# ChristmasTree.net
KiCad netlist of a schematic drawn in Altium Designer
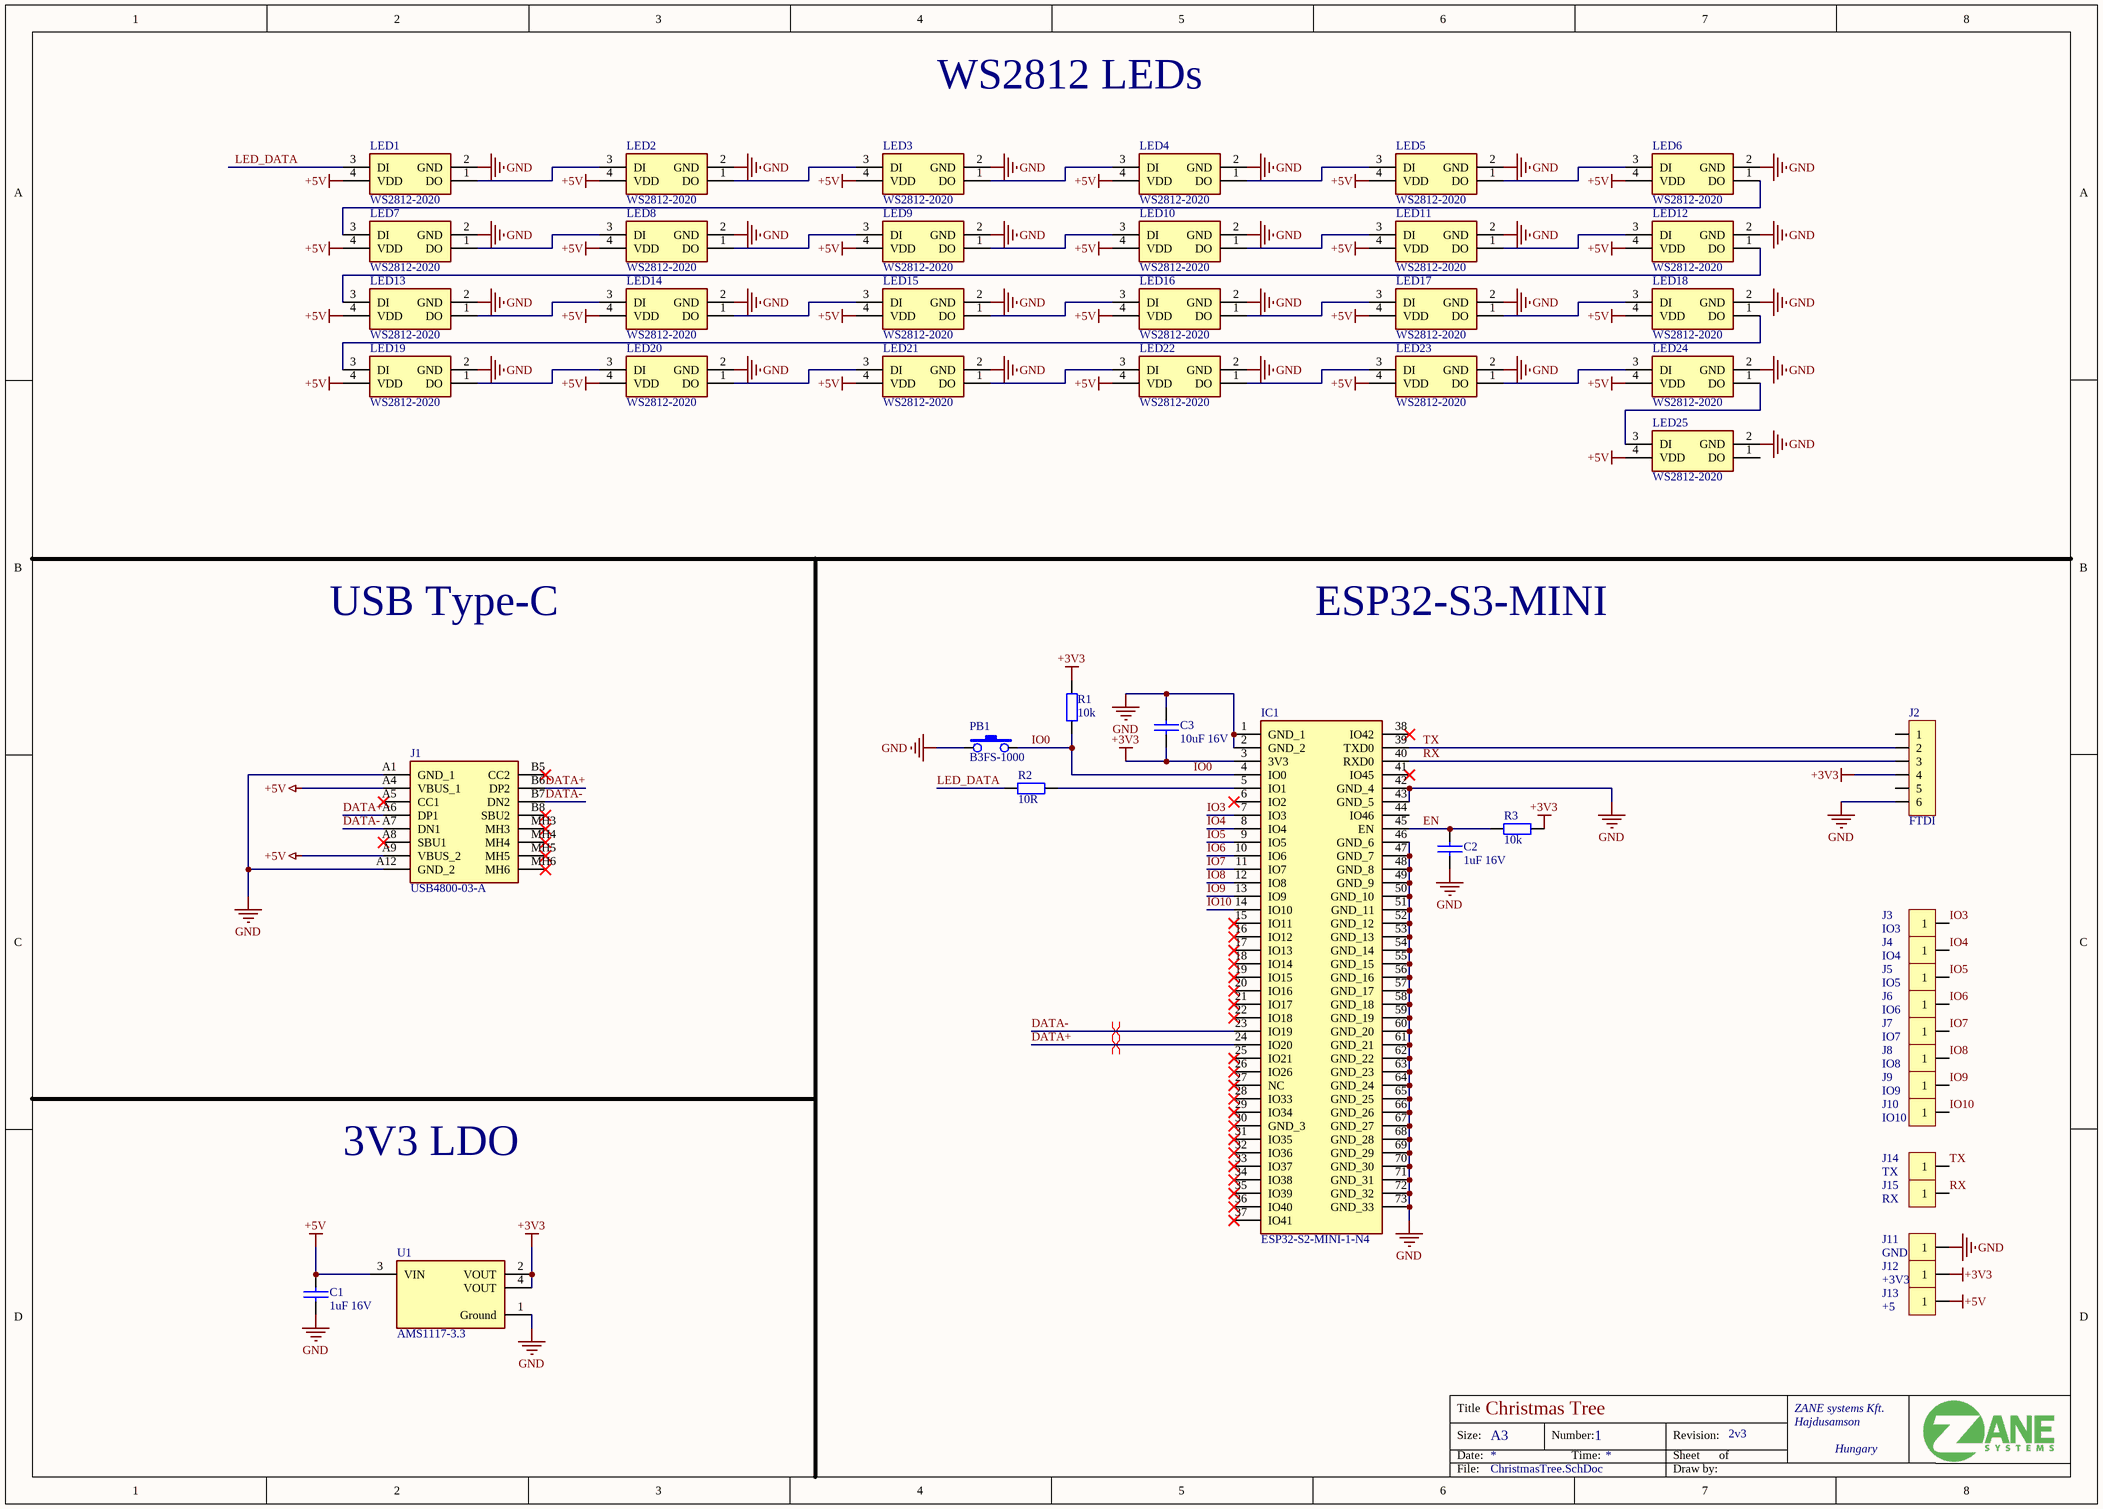
[diagram p0: ChristmasTree.SchDoc]

(export (version "E")
  (design (tool "Eeschema 10.0.6"))
  (components
    (comp (ref "C1")
      (value "1uF 16V")
      (footprint "Z_0603_C")
      (description "=Value")
      (fields (field (name "MF") "SAMSUNG"))
      (libsource (lib "miniscanner_schlib") (part "CAP_0805"))
    )
    (comp (ref "C2")
      (value "1uF 16V")
      (footprint "Z_0603_C")
      (description "=Value")
      (fields (field (name "MF") "SAMSUNG"))
      (libsource (lib "miniscanner_schlib") (part "CAP_0805"))
    )
    (comp (ref "C3")
      (value "10uF 16V")
      (footprint "Z_0603_C")
      (description "=Value")
      (fields (field (name "MF") "SAMSUNG"))
      (libsource (lib "miniscanner_schlib") (part "CAP_0805"))
    )
    (comp (ref "IC1")
      (value "ESP32-S2-MINI-1-N4")
      (footprint "SamacSys:ESP32S2MINI1N4")
      (description "Integrated Circuit")
      (fields (field (name "MOUSER PART NUMBER") "356-ESP32-S2-MINI-1"))
      (libsource (lib "SamacSys") (part "ESP32-S2-MINI-1-N4"))
    )
    (comp (ref "J1")
      (value "USB4800-03-A")
      (footprint "USB480003A")
      (description "Connector")
      (libsource (lib "*") (part "USB4800-03-A"))
    )
    (comp (ref "J2")
      (value "FTDI")
      (footprint "TUSKE1X6_2.54MM")
      (libsource (lib "zane_sch_lib") (part "CON6"))
    )
    (comp (ref "J3") (value "IO3") (footprint "SMD_PAD") (libsource (lib "zane_sch_lib") (part "CON1")))
    (comp (ref "J4") (value "IO4") (footprint "SMD_PAD") (libsource (lib "zane_sch_lib") (part "CON1")))
    (comp (ref "J5") (value "IO5") (footprint "SMD_PAD") (libsource (lib "zane_sch_lib") (part "CON1")))
    (comp (ref "J6") (value "IO6") (footprint "SMD_PAD") (libsource (lib "zane_sch_lib") (part "CON1")))
    (comp (ref "J7") (value "IO7") (footprint "SMD_PAD") (libsource (lib "zane_sch_lib") (part "CON1")))
    (comp (ref "J8") (value "IO8") (footprint "SMD_PAD") (libsource (lib "zane_sch_lib") (part "CON1")))
    (comp (ref "J9") (value "IO9") (footprint "SMD_PAD") (libsource (lib "zane_sch_lib") (part "CON1")))
    (comp (ref "J10") (value "IO10") (footprint "SMD_PAD") (libsource (lib "zane_sch_lib") (part "CON1")))
    (comp (ref "J11") (value "GND") (footprint "SMD_PAD") (libsource (lib "zane_sch_lib") (part "CON1")))
    (comp (ref "J12") (value "+3V3") (footprint "SMD_PAD") (libsource (lib "zane_sch_lib") (part "CON1")))
    (comp (ref "J13") (value "+5") (footprint "SMD_PAD") (libsource (lib "zane_sch_lib") (part "CON1")))
    (comp (ref "J14") (value "TX") (footprint "SMD_PAD") (libsource (lib "zane_sch_lib") (part "CON1")))
    (comp (ref "J15") (value "RX") (footprint "SMD_PAD") (libsource (lib "zane_sch_lib") (part "CON1")))
    (comp (ref "LED1")
      (value "WS2812-2020")
      (footprint "WS28122020")
      (description "LED")
      (libsource (lib "*") (part "WS2812-2020"))
    )
    (comp (ref "LED2")
      (value "WS2812-2020")
      (footprint "WS28122020")
      (description "LED")
      (libsource (lib "*") (part "WS2812-2020"))
    )
    (comp (ref "LED3")
      (value "WS2812-2020")
      (footprint "WS28122020")
      (description "LED")
      (libsource (lib "*") (part "WS2812-2020"))
    )
    (comp (ref "LED4")
      (value "WS2812-2020")
      (footprint "WS28122020")
      (description "LED")
      (libsource (lib "*") (part "WS2812-2020"))
    )
    (comp (ref "LED5")
      (value "WS2812-2020")
      (footprint "WS28122020")
      (description "LED")
      (libsource (lib "*") (part "WS2812-2020"))
    )
    (comp (ref "LED6")
      (value "WS2812-2020")
      (footprint "WS28122020")
      (description "LED")
      (libsource (lib "*") (part "WS2812-2020"))
    )
    (comp (ref "LED7")
      (value "WS2812-2020")
      (footprint "WS28122020")
      (description "LED")
      (libsource (lib "*") (part "WS2812-2020"))
    )
    (comp (ref "LED8")
      (value "WS2812-2020")
      (footprint "WS28122020")
      (description "LED")
      (libsource (lib "*") (part "WS2812-2020"))
    )
    (comp (ref "LED9")
      (value "WS2812-2020")
      (footprint "WS28122020")
      (description "LED")
      (libsource (lib "*") (part "WS2812-2020"))
    )
    (comp (ref "LED10")
      (value "WS2812-2020")
      (footprint "WS28122020")
      (description "LED")
      (libsource (lib "*") (part "WS2812-2020"))
    )
    (comp (ref "LED11")
      (value "WS2812-2020")
      (footprint "WS28122020")
      (description "LED")
      (libsource (lib "*") (part "WS2812-2020"))
    )
    (comp (ref "LED12")
      (value "WS2812-2020")
      (footprint "WS28122020")
      (description "LED")
      (libsource (lib "*") (part "WS2812-2020"))
    )
    (comp (ref "LED13")
      (value "WS2812-2020")
      (footprint "WS28122020")
      (description "LED")
      (libsource (lib "*") (part "WS2812-2020"))
    )
    (comp (ref "LED14")
      (value "WS2812-2020")
      (footprint "WS28122020")
      (description "LED")
      (libsource (lib "*") (part "WS2812-2020"))
    )
    (comp (ref "LED15")
      (value "WS2812-2020")
      (footprint "WS28122020")
      (description "LED")
      (libsource (lib "*") (part "WS2812-2020"))
    )
    (comp (ref "LED16")
      (value "WS2812-2020")
      (footprint "WS28122020")
      (description "LED")
      (libsource (lib "*") (part "WS2812-2020"))
    )
    (comp (ref "LED17")
      (value "WS2812-2020")
      (footprint "WS28122020")
      (description "LED")
      (libsource (lib "*") (part "WS2812-2020"))
    )
    (comp (ref "LED18")
      (value "WS2812-2020")
      (footprint "WS28122020")
      (description "LED")
      (libsource (lib "*") (part "WS2812-2020"))
    )
    (comp (ref "LED19")
      (value "WS2812-2020")
      (footprint "WS28122020")
      (description "LED")
      (libsource (lib "*") (part "WS2812-2020"))
    )
    (comp (ref "LED20")
      (value "WS2812-2020")
      (footprint "WS28122020")
      (description "LED")
      (libsource (lib "*") (part "WS2812-2020"))
    )
    (comp (ref "LED21")
      (value "WS2812-2020")
      (footprint "WS28122020")
      (description "LED")
      (libsource (lib "*") (part "WS2812-2020"))
    )
    (comp (ref "LED22")
      (value "WS2812-2020")
      (footprint "WS28122020")
      (description "LED")
      (libsource (lib "*") (part "WS2812-2020"))
    )
    (comp (ref "LED23")
      (value "WS2812-2020")
      (footprint "WS28122020")
      (description "LED")
      (libsource (lib "*") (part "WS2812-2020"))
    )
    (comp (ref "LED24")
      (value "WS2812-2020")
      (footprint "WS28122020")
      (description "LED")
      (libsource (lib "*") (part "WS2812-2020"))
    )
    (comp (ref "LED25")
      (value "WS2812-2020")
      (footprint "WS28122020")
      (description "LED")
      (libsource (lib "*") (part "WS2812-2020"))
    )
    (comp (ref "PB1")
      (value "B3FS-1000")
      (footprint "dtsm3")
      (description "Push Button")
      (libsource (lib "zane_sch_lib") (part "Push Button 2pin"))
    )
    (comp (ref "R1")
      (value "10k")
      (footprint "z_0603_r")
      (fields (field (name "MF") "ROYAL OHM"))
      (libsource (lib "") (part "Resistor_1"))
    )
    (comp (ref "R2")
      (value "10R")
      (footprint "z_0603_r")
      (fields (field (name "MF") "ROYAL OHM"))
      (libsource (lib "fit5mini_01") (part "Resistor"))
    )
    (comp (ref "R3")
      (value "10k")
      (footprint "z_0603_r")
      (fields (field (name "MF") "ROYAL OHM"))
      (libsource (lib "fit5mini_01") (part "Resistor"))
    )
    (comp (ref "U1")
      (value "AMS1117-3.3")
      (footprint "FP-AMS1117-IPC_C")
      (description "LDO Voltage Regulators 1A, 3.3V")
      (fields
        (field (name "OCTOPART") "https://octopart.com/ams1117-3.3-advanced+monolithic+systems-25899300")
        (field (name "MANUFACTURER") "Advanced Monolithic Systems")
      )
      (libsource (lib "Altium Content Vault") (part "8bdbb5f8e77002000e30dd2845d0354"))
    )
  )
  (nets
    (net (code "1") (name "+3V3") (class "Default")
      (node (ref "C3") (pin "1") (pinfunction "1_1") (pintype "passive"))
      (node (ref "IC1") (pin "3") (pinfunction "3V3_3") (pintype "passive"))
      (node (ref "J12") (pin "1") (pinfunction "1_1") (pintype "passive"))
      (node (ref "J2") (pin "4") (pinfunction "4_4") (pintype "passive"))
      (node (ref "R1") (pin "2") (pinfunction "2_2") (pintype "passive"))
      (node (ref "R3") (pin "1") (pinfunction "1_1") (pintype "passive"))
      (node (ref "U1") (pin "2") (pinfunction "VOUT_2") (pintype "passive"))
      (node (ref "U1") (pin "4") (pinfunction "VOUT_4") (pintype "passive"))
    )
    (net (code "2") (name "+5V") (class "Default")
      (node (ref "C1") (pin "1") (pinfunction "1_1") (pintype "passive"))
      (node (ref "J1") (pin "A4") (pinfunction "VBUS_1_A4") (pintype "passive"))
      (node (ref "J1") (pin "A9") (pinfunction "VBUS_2_A9") (pintype "passive"))
      (node (ref "J13") (pin "1") (pinfunction "1_1") (pintype "passive"))
      (node (ref "LED1") (pin "4") (pinfunction "VDD_4") (pintype "passive"))
      (node (ref "LED10") (pin "4") (pinfunction "VDD_4") (pintype "passive"))
      (node (ref "LED11") (pin "4") (pinfunction "VDD_4") (pintype "passive"))
      (node (ref "LED12") (pin "4") (pinfunction "VDD_4") (pintype "passive"))
      (node (ref "LED13") (pin "4") (pinfunction "VDD_4") (pintype "passive"))
      (node (ref "LED14") (pin "4") (pinfunction "VDD_4") (pintype "passive"))
      (node (ref "LED15") (pin "4") (pinfunction "VDD_4") (pintype "passive"))
      (node (ref "LED16") (pin "4") (pinfunction "VDD_4") (pintype "passive"))
      (node (ref "LED17") (pin "4") (pinfunction "VDD_4") (pintype "passive"))
      (node (ref "LED18") (pin "4") (pinfunction "VDD_4") (pintype "passive"))
      (node (ref "LED19") (pin "4") (pinfunction "VDD_4") (pintype "passive"))
      (node (ref "LED2") (pin "4") (pinfunction "VDD_4") (pintype "passive"))
      (node (ref "LED20") (pin "4") (pinfunction "VDD_4") (pintype "passive"))
      (node (ref "LED21") (pin "4") (pinfunction "VDD_4") (pintype "passive"))
      (node (ref "LED22") (pin "4") (pinfunction "VDD_4") (pintype "passive"))
      (node (ref "LED23") (pin "4") (pinfunction "VDD_4") (pintype "passive"))
      (node (ref "LED24") (pin "4") (pinfunction "VDD_4") (pintype "passive"))
      (node (ref "LED25") (pin "4") (pinfunction "VDD_4") (pintype "passive"))
      (node (ref "LED3") (pin "4") (pinfunction "VDD_4") (pintype "passive"))
      (node (ref "LED4") (pin "4") (pinfunction "VDD_4") (pintype "passive"))
      (node (ref "LED5") (pin "4") (pinfunction "VDD_4") (pintype "passive"))
      (node (ref "LED6") (pin "4") (pinfunction "VDD_4") (pintype "passive"))
      (node (ref "LED7") (pin "4") (pinfunction "VDD_4") (pintype "passive"))
      (node (ref "LED8") (pin "4") (pinfunction "VDD_4") (pintype "passive"))
      (node (ref "LED9") (pin "4") (pinfunction "VDD_4") (pintype "passive"))
      (node (ref "U1") (pin "3") (pinfunction "VIN_3") (pintype "power_in"))
    )
    (net (code "3") (name "/DATA+") (class "Default")
      (node (ref "IC1") (pin "24") (pinfunction "IO20_24") (pintype "passive"))
      (node (ref "J1") (pin "A6") (pinfunction "DP1_A6") (pintype "passive"))
      (node (ref "J1") (pin "B6") (pinfunction "DP2_B6") (pintype "passive"))
    )
    (net (code "4") (name "/DATA-") (class "Default")
      (node (ref "IC1") (pin "23") (pinfunction "IO19_23") (pintype "passive"))
      (node (ref "J1") (pin "A7") (pinfunction "DN1_A7") (pintype "passive"))
      (node (ref "J1") (pin "B7") (pinfunction "DN2_B7") (pintype "passive"))
    )
    (net (code "5") (name "/EN") (class "Default")
      (node (ref "C2") (pin "1") (pinfunction "1_1") (pintype "passive"))
      (node (ref "IC1") (pin "45") (pinfunction "EN_45") (pintype "passive"))
      (node (ref "R3") (pin "2") (pinfunction "2_2") (pintype "passive"))
    )
    (net (code "6") (name "/IO0") (class "Default")
      (node (ref "IC1") (pin "4") (pinfunction "IO0_4") (pintype "passive"))
      (node (ref "PB1") (pin "2") (pintype "passive"))
      (node (ref "R1") (pin "1") (pinfunction "1_1") (pintype "passive"))
    )
    (net (code "7") (name "/IO3") (class "Default")
      (node (ref "IC1") (pin "7") (pinfunction "IO3_7") (pintype "passive"))
      (node (ref "J3") (pin "1") (pinfunction "1_1") (pintype "passive"))
    )
    (net (code "8") (name "/IO4") (class "Default")
      (node (ref "IC1") (pin "8") (pinfunction "IO4_8") (pintype "passive"))
      (node (ref "J4") (pin "1") (pinfunction "1_1") (pintype "passive"))
    )
    (net (code "9") (name "/IO5") (class "Default")
      (node (ref "IC1") (pin "9") (pinfunction "IO5_9") (pintype "passive"))
      (node (ref "J5") (pin "1") (pinfunction "1_1") (pintype "passive"))
    )
    (net (code "10") (name "/IO6") (class "Default")
      (node (ref "IC1") (pin "10") (pinfunction "IO6_10") (pintype "passive"))
      (node (ref "J6") (pin "1") (pinfunction "1_1") (pintype "passive"))
    )
    (net (code "11") (name "/IO7") (class "Default")
      (node (ref "IC1") (pin "11") (pinfunction "IO7_11") (pintype "passive"))
      (node (ref "J7") (pin "1") (pinfunction "1_1") (pintype "passive"))
    )
    (net (code "12") (name "/IO8") (class "Default")
      (node (ref "IC1") (pin "12") (pinfunction "IO8_12") (pintype "passive"))
      (node (ref "J8") (pin "1") (pinfunction "1_1") (pintype "passive"))
    )
    (net (code "13") (name "/IO9") (class "Default")
      (node (ref "IC1") (pin "13") (pinfunction "IO9_13") (pintype "passive"))
      (node (ref "J9") (pin "1") (pinfunction "1_1") (pintype "passive"))
    )
    (net (code "14") (name "/IO10") (class "Default")
      (node (ref "IC1") (pin "14") (pinfunction "IO10_14") (pintype "passive"))
      (node (ref "J10") (pin "1") (pinfunction "1_1") (pintype "passive"))
    )
    (net (code "15") (name "/LED_DATA") (class "Default")
      (node (ref "LED1") (pin "3") (pinfunction "DI_3") (pintype "passive"))
      (node (ref "R2") (pin "2") (pinfunction "2_2") (pintype "passive"))
    )
    (net (code "16") (name "/RX") (class "Default")
      (node (ref "IC1") (pin "40") (pinfunction "RXD0_40") (pintype "passive"))
      (node (ref "J15") (pin "1") (pinfunction "1_1") (pintype "passive"))
      (node (ref "J2") (pin "3") (pinfunction "3_3") (pintype "passive"))
    )
    (net (code "17") (name "/TX") (class "Default")
      (node (ref "IC1") (pin "39") (pinfunction "TXD0_39") (pintype "passive"))
      (node (ref "J14") (pin "1") (pinfunction "1_1") (pintype "passive"))
      (node (ref "J2") (pin "2") (pinfunction "2_2") (pintype "passive"))
    )
    (net (code "18") (name "GND") (class "Default")
      (node (ref "C1") (pin "2") (pinfunction "2_2") (pintype "passive"))
      (node (ref "C2") (pin "2") (pinfunction "2_2") (pintype "passive"))
      (node (ref "C3") (pin "2") (pinfunction "2_2") (pintype "passive"))
      (node (ref "IC1") (pin "1") (pinfunction "GND_1_1") (pintype "passive"))
      (node (ref "IC1") (pin "2") (pinfunction "GND_2_2") (pintype "passive"))
      (node (ref "IC1") (pin "42") (pinfunction "GND_4_42") (pintype "passive"))
      (node (ref "IC1") (pin "43") (pinfunction "GND_5_43") (pintype "passive"))
      (node (ref "IC1") (pin "46") (pinfunction "GND_6_46") (pintype "passive"))
      (node (ref "IC1") (pin "47") (pinfunction "GND_7_47") (pintype "passive"))
      (node (ref "IC1") (pin "48") (pinfunction "GND_8_48") (pintype "passive"))
      (node (ref "IC1") (pin "49") (pinfunction "GND_9_49") (pintype "passive"))
      (node (ref "IC1") (pin "50") (pinfunction "GND_10_50") (pintype "passive"))
      (node (ref "IC1") (pin "51") (pinfunction "GND_11_51") (pintype "passive"))
      (node (ref "IC1") (pin "52") (pinfunction "GND_12_52") (pintype "passive"))
      (node (ref "IC1") (pin "53") (pinfunction "GND_13_53") (pintype "passive"))
      (node (ref "IC1") (pin "54") (pinfunction "GND_14_54") (pintype "passive"))
      (node (ref "IC1") (pin "55") (pinfunction "GND_15_55") (pintype "passive"))
      (node (ref "IC1") (pin "56") (pinfunction "GND_16_56") (pintype "passive"))
      (node (ref "IC1") (pin "57") (pinfunction "GND_17_57") (pintype "passive"))
      (node (ref "IC1") (pin "58") (pinfunction "GND_18_58") (pintype "passive"))
      (node (ref "IC1") (pin "59") (pinfunction "GND_19_59") (pintype "passive"))
      (node (ref "IC1") (pin "60") (pinfunction "GND_20_60") (pintype "passive"))
      (node (ref "IC1") (pin "61") (pinfunction "GND_21_61") (pintype "passive"))
      (node (ref "IC1") (pin "62") (pinfunction "GND_22_62") (pintype "passive"))
      (node (ref "IC1") (pin "63") (pinfunction "GND_23_63") (pintype "passive"))
      (node (ref "IC1") (pin "64") (pinfunction "GND_24_64") (pintype "passive"))
      (node (ref "IC1") (pin "65") (pinfunction "GND_25_65") (pintype "passive"))
      (node (ref "IC1") (pin "66") (pinfunction "GND_26_66") (pintype "passive"))
      (node (ref "IC1") (pin "67") (pinfunction "GND_27_67") (pintype "passive"))
      (node (ref "IC1") (pin "68") (pinfunction "GND_28_68") (pintype "passive"))
      (node (ref "IC1") (pin "69") (pinfunction "GND_29_69") (pintype "passive"))
      (node (ref "IC1") (pin "70") (pinfunction "GND_30_70") (pintype "passive"))
      (node (ref "IC1") (pin "71") (pinfunction "GND_31_71") (pintype "passive"))
      (node (ref "IC1") (pin "72") (pinfunction "GND_32_72") (pintype "passive"))
      (node (ref "IC1") (pin "73") (pinfunction "GND_33_73") (pintype "passive"))
      (node (ref "J1") (pin "A1") (pinfunction "GND_1_A1") (pintype "passive"))
      (node (ref "J1") (pin "A12") (pinfunction "GND_2_A12") (pintype "passive"))
      (node (ref "J11") (pin "1") (pinfunction "1_1") (pintype "passive"))
      (node (ref "J2") (pin "6") (pinfunction "6_6") (pintype "passive"))
      (node (ref "LED1") (pin "2") (pinfunction "GND_2") (pintype "passive"))
      (node (ref "LED10") (pin "2") (pinfunction "GND_2") (pintype "passive"))
      (node (ref "LED11") (pin "2") (pinfunction "GND_2") (pintype "passive"))
      (node (ref "LED12") (pin "2") (pinfunction "GND_2") (pintype "passive"))
      (node (ref "LED13") (pin "2") (pinfunction "GND_2") (pintype "passive"))
      (node (ref "LED14") (pin "2") (pinfunction "GND_2") (pintype "passive"))
      (node (ref "LED15") (pin "2") (pinfunction "GND_2") (pintype "passive"))
      (node (ref "LED16") (pin "2") (pinfunction "GND_2") (pintype "passive"))
      (node (ref "LED17") (pin "2") (pinfunction "GND_2") (pintype "passive"))
      (node (ref "LED18") (pin "2") (pinfunction "GND_2") (pintype "passive"))
      (node (ref "LED19") (pin "2") (pinfunction "GND_2") (pintype "passive"))
      (node (ref "LED2") (pin "2") (pinfunction "GND_2") (pintype "passive"))
      (node (ref "LED20") (pin "2") (pinfunction "GND_2") (pintype "passive"))
      (node (ref "LED21") (pin "2") (pinfunction "GND_2") (pintype "passive"))
      (node (ref "LED22") (pin "2") (pinfunction "GND_2") (pintype "passive"))
      (node (ref "LED23") (pin "2") (pinfunction "GND_2") (pintype "passive"))
      (node (ref "LED24") (pin "2") (pinfunction "GND_2") (pintype "passive"))
      (node (ref "LED25") (pin "2") (pinfunction "GND_2") (pintype "passive"))
      (node (ref "LED3") (pin "2") (pinfunction "GND_2") (pintype "passive"))
      (node (ref "LED4") (pin "2") (pinfunction "GND_2") (pintype "passive"))
      (node (ref "LED5") (pin "2") (pinfunction "GND_2") (pintype "passive"))
      (node (ref "LED6") (pin "2") (pinfunction "GND_2") (pintype "passive"))
      (node (ref "LED7") (pin "2") (pinfunction "GND_2") (pintype "passive"))
      (node (ref "LED8") (pin "2") (pinfunction "GND_2") (pintype "passive"))
      (node (ref "LED9") (pin "2") (pinfunction "GND_2") (pintype "passive"))
      (node (ref "PB1") (pin "1") (pintype "passive"))
      (node (ref "U1") (pin "1") (pinfunction "Ground_1") (pintype "power_in"))
    )
    (net (code "19") (name "Net-(IC1-IO1)") (class "Default")
      (node (ref "IC1") (pin "5") (pinfunction "IO1_5") (pintype "passive"))
      (node (ref "R2") (pin "1") (pinfunction "1_1") (pintype "passive"))
    )
    (net (code "20") (name "Net-(LED1-DO)") (class "Default")
      (node (ref "LED1") (pin "1") (pinfunction "DO_1") (pintype "passive"))
      (node (ref "LED2") (pin "3") (pinfunction "DI_3") (pintype "passive"))
    )
    (net (code "21") (name "Net-(LED2-DO)") (class "Default")
      (node (ref "LED2") (pin "1") (pinfunction "DO_1") (pintype "passive"))
      (node (ref "LED3") (pin "3") (pinfunction "DI_3") (pintype "passive"))
    )
    (net (code "22") (name "Net-(LED3-DO)") (class "Default")
      (node (ref "LED3") (pin "1") (pinfunction "DO_1") (pintype "passive"))
      (node (ref "LED4") (pin "3") (pinfunction "DI_3") (pintype "passive"))
    )
    (net (code "23") (name "Net-(LED4-DO)") (class "Default")
      (node (ref "LED4") (pin "1") (pinfunction "DO_1") (pintype "passive"))
      (node (ref "LED5") (pin "3") (pinfunction "DI_3") (pintype "passive"))
    )
    (net (code "24") (name "Net-(LED5-DO)") (class "Default")
      (node (ref "LED5") (pin "1") (pinfunction "DO_1") (pintype "passive"))
      (node (ref "LED6") (pin "3") (pinfunction "DI_3") (pintype "passive"))
    )
    (net (code "25") (name "Net-(LED6-DO)") (class "Default")
      (node (ref "LED6") (pin "1") (pinfunction "DO_1") (pintype "passive"))
      (node (ref "LED7") (pin "3") (pinfunction "DI_3") (pintype "passive"))
    )
    (net (code "26") (name "Net-(LED7-DO)") (class "Default")
      (node (ref "LED7") (pin "1") (pinfunction "DO_1") (pintype "passive"))
      (node (ref "LED8") (pin "3") (pinfunction "DI_3") (pintype "passive"))
    )
    (net (code "27") (name "Net-(LED8-DO)") (class "Default")
      (node (ref "LED8") (pin "1") (pinfunction "DO_1") (pintype "passive"))
      (node (ref "LED9") (pin "3") (pinfunction "DI_3") (pintype "passive"))
    )
    (net (code "28") (name "Net-(LED10-DI)") (class "Default")
      (node (ref "LED10") (pin "3") (pinfunction "DI_3") (pintype "passive"))
      (node (ref "LED9") (pin "1") (pinfunction "DO_1") (pintype "passive"))
    )
    (net (code "29") (name "Net-(LED10-DO)") (class "Default")
      (node (ref "LED10") (pin "1") (pinfunction "DO_1") (pintype "passive"))
      (node (ref "LED11") (pin "3") (pinfunction "DI_3") (pintype "passive"))
    )
    (net (code "30") (name "Net-(LED11-DO)") (class "Default")
      (node (ref "LED11") (pin "1") (pinfunction "DO_1") (pintype "passive"))
      (node (ref "LED12") (pin "3") (pinfunction "DI_3") (pintype "passive"))
    )
    (net (code "31") (name "Net-(LED12-DO)") (class "Default")
      (node (ref "LED12") (pin "1") (pinfunction "DO_1") (pintype "passive"))
      (node (ref "LED13") (pin "3") (pinfunction "DI_3") (pintype "passive"))
    )
    (net (code "32") (name "Net-(LED13-DO)") (class "Default")
      (node (ref "LED13") (pin "1") (pinfunction "DO_1") (pintype "passive"))
      (node (ref "LED14") (pin "3") (pinfunction "DI_3") (pintype "passive"))
    )
    (net (code "33") (name "Net-(LED14-DO)") (class "Default")
      (node (ref "LED14") (pin "1") (pinfunction "DO_1") (pintype "passive"))
      (node (ref "LED15") (pin "3") (pinfunction "DI_3") (pintype "passive"))
    )
    (net (code "34") (name "Net-(LED15-DO)") (class "Default")
      (node (ref "LED15") (pin "1") (pinfunction "DO_1") (pintype "passive"))
      (node (ref "LED16") (pin "3") (pinfunction "DI_3") (pintype "passive"))
    )
    (net (code "35") (name "Net-(LED16-DO)") (class "Default")
      (node (ref "LED16") (pin "1") (pinfunction "DO_1") (pintype "passive"))
      (node (ref "LED17") (pin "3") (pinfunction "DI_3") (pintype "passive"))
    )
    (net (code "36") (name "Net-(LED17-DO)") (class "Default")
      (node (ref "LED17") (pin "1") (pinfunction "DO_1") (pintype "passive"))
      (node (ref "LED18") (pin "3") (pinfunction "DI_3") (pintype "passive"))
    )
    (net (code "37") (name "Net-(LED18-DO)") (class "Default")
      (node (ref "LED18") (pin "1") (pinfunction "DO_1") (pintype "passive"))
      (node (ref "LED19") (pin "3") (pinfunction "DI_3") (pintype "passive"))
    )
    (net (code "38") (name "Net-(LED19-DO)") (class "Default")
      (node (ref "LED19") (pin "1") (pinfunction "DO_1") (pintype "passive"))
      (node (ref "LED20") (pin "3") (pinfunction "DI_3") (pintype "passive"))
    )
    (net (code "39") (name "Net-(LED20-DO)") (class "Default")
      (node (ref "LED20") (pin "1") (pinfunction "DO_1") (pintype "passive"))
      (node (ref "LED21") (pin "3") (pinfunction "DI_3") (pintype "passive"))
    )
    (net (code "40") (name "Net-(LED21-DO)") (class "Default")
      (node (ref "LED21") (pin "1") (pinfunction "DO_1") (pintype "passive"))
      (node (ref "LED22") (pin "3") (pinfunction "DI_3") (pintype "passive"))
    )
    (net (code "41") (name "Net-(LED22-DO)") (class "Default")
      (node (ref "LED22") (pin "1") (pinfunction "DO_1") (pintype "passive"))
      (node (ref "LED23") (pin "3") (pinfunction "DI_3") (pintype "passive"))
    )
    (net (code "42") (name "Net-(LED23-DO)") (class "Default")
      (node (ref "LED23") (pin "1") (pinfunction "DO_1") (pintype "passive"))
      (node (ref "LED24") (pin "3") (pinfunction "DI_3") (pintype "passive"))
    )
    (net (code "43") (name "Net-(LED24-DO)") (class "Default")
      (node (ref "LED24") (pin "1") (pinfunction "DO_1") (pintype "passive"))
      (node (ref "LED25") (pin "3") (pinfunction "DI_3") (pintype "passive"))
    )
    (net (code "44") (name "unconnected-(IC1-GND_3-Pad30)") (class "Default")
      (node (ref "IC1") (pin "30") (pinfunction "GND_3_30") (pintype "passive+no_connect"))
    )
    (net (code "45") (name "unconnected-(IC1-IO2-Pad6)") (class "Default")
      (node (ref "IC1") (pin "6") (pinfunction "IO2_6") (pintype "passive+no_connect"))
    )
    (net (code "46") (name "unconnected-(IC1-IO11-Pad15)") (class "Default")
      (node (ref "IC1") (pin "15") (pinfunction "IO11_15") (pintype "passive+no_connect"))
    )
    (net (code "47") (name "unconnected-(IC1-IO12-Pad16)") (class "Default")
      (node (ref "IC1") (pin "16") (pinfunction "IO12_16") (pintype "passive+no_connect"))
    )
    (net (code "48") (name "unconnected-(IC1-IO13-Pad17)") (class "Default")
      (node (ref "IC1") (pin "17") (pinfunction "IO13_17") (pintype "passive+no_connect"))
    )
    (net (code "49") (name "unconnected-(IC1-IO14-Pad18)") (class "Default")
      (node (ref "IC1") (pin "18") (pinfunction "IO14_18") (pintype "passive+no_connect"))
    )
    (net (code "50") (name "unconnected-(IC1-IO15-Pad19)") (class "Default")
      (node (ref "IC1") (pin "19") (pinfunction "IO15_19") (pintype "passive+no_connect"))
    )
    (net (code "51") (name "unconnected-(IC1-IO16-Pad20)") (class "Default")
      (node (ref "IC1") (pin "20") (pinfunction "IO16_20") (pintype "passive+no_connect"))
    )
    (net (code "52") (name "unconnected-(IC1-IO17-Pad21)") (class "Default")
      (node (ref "IC1") (pin "21") (pinfunction "IO17_21") (pintype "passive+no_connect"))
    )
    (net (code "53") (name "unconnected-(IC1-IO18-Pad22)") (class "Default")
      (node (ref "IC1") (pin "22") (pinfunction "IO18_22") (pintype "passive+no_connect"))
    )
    (net (code "54") (name "unconnected-(IC1-IO21-Pad25)") (class "Default")
      (node (ref "IC1") (pin "25") (pinfunction "IO21_25") (pintype "passive+no_connect"))
    )
    (net (code "55") (name "unconnected-(IC1-IO26-Pad26)") (class "Default")
      (node (ref "IC1") (pin "26") (pinfunction "IO26_26") (pintype "passive+no_connect"))
    )
    (net (code "56") (name "unconnected-(IC1-IO33-Pad28)") (class "Default")
      (node (ref "IC1") (pin "28") (pinfunction "IO33_28") (pintype "passive+no_connect"))
    )
    (net (code "57") (name "unconnected-(IC1-IO34-Pad29)") (class "Default")
      (node (ref "IC1") (pin "29") (pinfunction "IO34_29") (pintype "passive+no_connect"))
    )
    (net (code "58") (name "unconnected-(IC1-IO35-Pad31)") (class "Default")
      (node (ref "IC1") (pin "31") (pinfunction "IO35_31") (pintype "passive+no_connect"))
    )
    (net (code "59") (name "unconnected-(IC1-IO36-Pad32)") (class "Default")
      (node (ref "IC1") (pin "32") (pinfunction "IO36_32") (pintype "passive+no_connect"))
    )
    (net (code "60") (name "unconnected-(IC1-IO37-Pad33)") (class "Default")
      (node (ref "IC1") (pin "33") (pinfunction "IO37_33") (pintype "passive+no_connect"))
    )
    (net (code "61") (name "unconnected-(IC1-IO38-Pad34)") (class "Default")
      (node (ref "IC1") (pin "34") (pinfunction "IO38_34") (pintype "passive+no_connect"))
    )
    (net (code "62") (name "unconnected-(IC1-IO39-Pad35)") (class "Default")
      (node (ref "IC1") (pin "35") (pinfunction "IO39_35") (pintype "passive+no_connect"))
    )
    (net (code "63") (name "unconnected-(IC1-IO40-Pad36)") (class "Default")
      (node (ref "IC1") (pin "36") (pinfunction "IO40_36") (pintype "passive+no_connect"))
    )
    (net (code "64") (name "unconnected-(IC1-IO41-Pad37)") (class "Default")
      (node (ref "IC1") (pin "37") (pinfunction "IO41_37") (pintype "passive+no_connect"))
    )
    (net (code "65") (name "unconnected-(IC1-IO42-Pad38)") (class "Default")
      (node (ref "IC1") (pin "38") (pinfunction "IO42_38") (pintype "passive+no_connect"))
    )
    (net (code "66") (name "unconnected-(IC1-IO45-Pad41)") (class "Default")
      (node (ref "IC1") (pin "41") (pinfunction "IO45_41") (pintype "passive+no_connect"))
    )
    (net (code "67") (name "unconnected-(IC1-IO46-Pad44)") (class "Default")
      (node (ref "IC1") (pin "44") (pinfunction "IO46_44") (pintype "passive"))
    )
    (net (code "68") (name "unconnected-(IC1-NC-Pad27)") (class "Default")
      (node (ref "IC1") (pin "27") (pinfunction "NC_27") (pintype "passive+no_connect"))
    )
    (net (code "69") (name "unconnected-(J1-CC1-PadA5)") (class "Default")
      (node (ref "J1") (pin "A5") (pinfunction "CC1_A5") (pintype "passive+no_connect"))
    )
    (net (code "70") (name "unconnected-(J1-CC2-PadB5)") (class "Default")
      (node (ref "J1") (pin "B5") (pinfunction "CC2_B5") (pintype "passive+no_connect"))
    )
    (net (code "71") (name "unconnected-(J1-PadMH3)") (class "Default")
      (node (ref "J1") (pin "MH3") (pinfunction "MH3_MH3") (pintype "passive+no_connect"))
    )
    (net (code "72") (name "unconnected-(J1-PadMH4)") (class "Default")
      (node (ref "J1") (pin "MH4") (pinfunction "MH4_MH4") (pintype "passive+no_connect"))
    )
    (net (code "73") (name "unconnected-(J1-PadMH5)") (class "Default")
      (node (ref "J1") (pin "MH5") (pinfunction "MH5_MH5") (pintype "passive+no_connect"))
    )
    (net (code "74") (name "unconnected-(J1-PadMH6)") (class "Default")
      (node (ref "J1") (pin "MH6") (pinfunction "MH6_MH6") (pintype "passive+no_connect"))
    )
    (net (code "75") (name "unconnected-(J1-SBU1-PadA8)") (class "Default")
      (node (ref "J1") (pin "A8") (pinfunction "SBU1_A8") (pintype "passive+no_connect"))
    )
    (net (code "76") (name "unconnected-(J1-SBU2-PadB8)") (class "Default")
      (node (ref "J1") (pin "B8") (pinfunction "SBU2_B8") (pintype "passive+no_connect"))
    )
    (net (code "77") (name "unconnected-(J2-Pad1)") (class "Default")
      (node (ref "J2") (pin "1") (pinfunction "1_1") (pintype "passive"))
    )
    (net (code "78") (name "unconnected-(J2-Pad5)") (class "Default")
      (node (ref "J2") (pin "5") (pinfunction "5_5") (pintype "passive"))
    )
    (net (code "79") (name "unconnected-(LED25-DO-Pad1)") (class "Default")
      (node (ref "LED25") (pin "1") (pinfunction "DO_1") (pintype "passive"))
    )
  )
)
